# Input_analog.net
KiCad netlist of a schematic drawn in Altium Designer
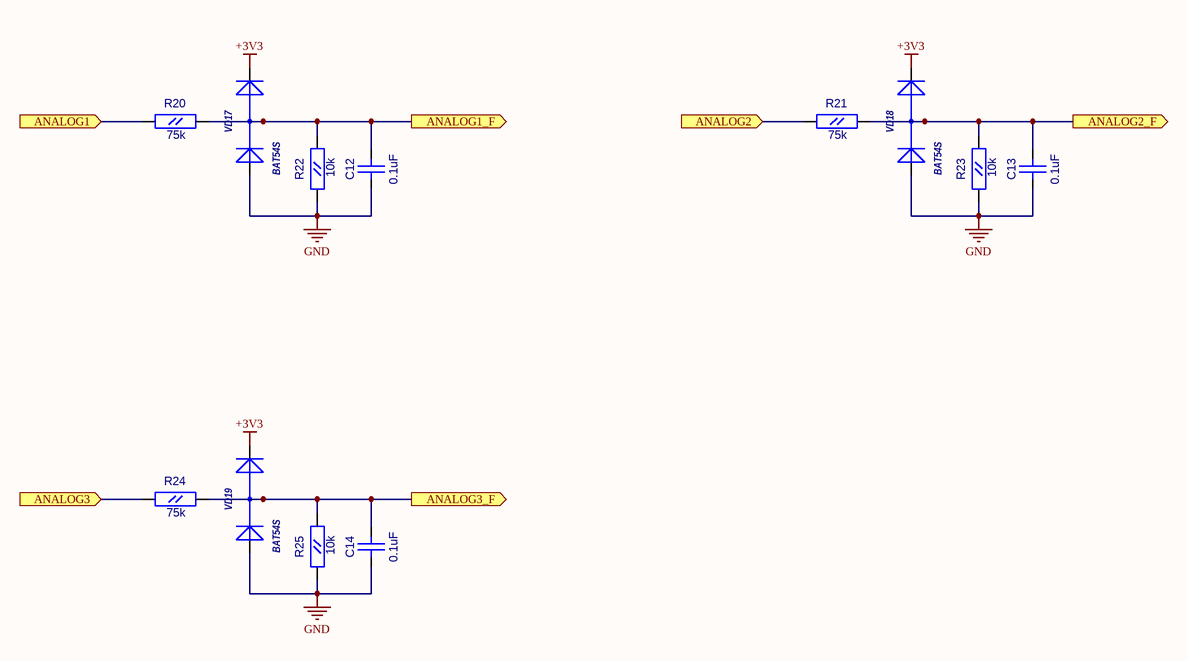
[diagram p0: Input_analog.SchDoc]

(export (version "E")
  (design (tool "Eeschema 10.0.6"))
  (components
    (comp (ref "C12")
      (value "0.1uF")
      (footprint "CC0603")
      (description "CC0603")
      (libsource (lib "gprs_modem_2") (part "CC0603"))
    )
    (comp (ref "C13")
      (value "0.1uF")
      (footprint "CC0603")
      (description "CC0603")
      (libsource (lib "gprs_modem_2") (part "CC0603"))
    )
    (comp (ref "C14")
      (value "0.1uF")
      (footprint "CC0603")
      (description "CC0603")
      (libsource (lib "gprs_modem_2") (part "CC0603"))
    )
    (comp (ref "R20")
      (value "75k")
      (footprint "RC0603")
      (description "RC0603")
      (libsource (lib "gprs_modem_2") (part "RC0603"))
    )
    (comp (ref "R21")
      (value "75k")
      (footprint "RC0603")
      (description "RC0603")
      (libsource (lib "gprs_modem_2") (part "RC0603"))
    )
    (comp (ref "R22")
      (value "10k")
      (footprint "RC0603")
      (description "RC0603")
      (libsource (lib "gprs_modem_2") (part "RC0603"))
    )
    (comp (ref "R23")
      (value "10k")
      (footprint "RC0603")
      (description "RC0603")
      (libsource (lib "gprs_modem_2") (part "RC0603"))
    )
    (comp (ref "R24")
      (value "75k")
      (footprint "RC0603")
      (description "RC0603")
      (libsource (lib "gprs_modem_2") (part "RC0603"))
    )
    (comp (ref "R25")
      (value "10k")
      (footprint "RC0603")
      (description "RC0603")
      (libsource (lib "gprs_modem_2") (part "RC0603"))
    )
    (comp (ref "VD17")
      (value "BAT54S")
      (footprint "SOT-23(GSD)")
      (description "1.0 Ampere General Purpose Rectifier")
      (libsource (lib "gprs_modem_2") (part "BAT54S"))
    )
    (comp (ref "VD18")
      (value "BAT54S")
      (footprint "SOT-23(GSD)")
      (description "1.0 Ampere General Purpose Rectifier")
      (libsource (lib "gprs_modem_2") (part "BAT54S"))
    )
    (comp (ref "VD19")
      (value "BAT54S")
      (footprint "SOT-23(GSD)")
      (description "1.0 Ampere General Purpose Rectifier")
      (libsource (lib "gprs_modem_2") (part "BAT54S"))
    )
  )
  (nets
    (net (code "1") (name "+3V3") (class "Default")
      (node (ref "VD17") (pin "2") (pinfunction "K_2") (pintype "passive"))
      (node (ref "VD18") (pin "2") (pinfunction "K_2") (pintype "passive"))
      (node (ref "VD19") (pin "2") (pinfunction "K_2") (pintype "passive"))
    )
    (net (code "2") (name "/ANALOG1") (class "Default")
      (node (ref "R20") (pin "1") (pinfunction "A_1") (pintype "passive"))
    )
    (net (code "3") (name "/ANALOG1_F") (class "Default")
      (node (ref "C12") (pin "2") (pinfunction "B_2") (pintype "passive"))
      (node (ref "R20") (pin "2") (pinfunction "B_2") (pintype "passive"))
      (node (ref "R22") (pin "2") (pinfunction "B_2") (pintype "passive"))
      (node (ref "VD17") (pin "3") (pinfunction "AK_3") (pintype "passive"))
    )
    (net (code "4") (name "/ANALOG2") (class "Default")
      (node (ref "R21") (pin "1") (pinfunction "A_1") (pintype "passive"))
    )
    (net (code "5") (name "/ANALOG2_F") (class "Default")
      (node (ref "C13") (pin "2") (pinfunction "B_2") (pintype "passive"))
      (node (ref "R21") (pin "2") (pinfunction "B_2") (pintype "passive"))
      (node (ref "R23") (pin "2") (pinfunction "B_2") (pintype "passive"))
      (node (ref "VD18") (pin "3") (pinfunction "AK_3") (pintype "passive"))
    )
    (net (code "6") (name "/ANALOG3") (class "Default")
      (node (ref "R24") (pin "1") (pinfunction "A_1") (pintype "passive"))
    )
    (net (code "7") (name "/ANALOG3_F") (class "Default")
      (node (ref "C14") (pin "2") (pinfunction "B_2") (pintype "passive"))
      (node (ref "R24") (pin "2") (pinfunction "B_2") (pintype "passive"))
      (node (ref "R25") (pin "2") (pinfunction "B_2") (pintype "passive"))
      (node (ref "VD19") (pin "3") (pinfunction "AK_3") (pintype "passive"))
    )
    (net (code "8") (name "GND") (class "Default")
      (node (ref "C12") (pin "1") (pinfunction "A_1") (pintype "passive"))
      (node (ref "C13") (pin "1") (pinfunction "A_1") (pintype "passive"))
      (node (ref "C14") (pin "1") (pinfunction "A_1") (pintype "passive"))
      (node (ref "R22") (pin "1") (pinfunction "A_1") (pintype "passive"))
      (node (ref "R23") (pin "1") (pinfunction "A_1") (pintype "passive"))
      (node (ref "R25") (pin "1") (pinfunction "A_1") (pintype "passive"))
      (node (ref "VD17") (pin "1") (pinfunction "A_1") (pintype "passive"))
      (node (ref "VD18") (pin "1") (pinfunction "A_1") (pintype "passive"))
      (node (ref "VD19") (pin "1") (pinfunction "A_1") (pintype "passive"))
    )
  )
)
